# Controller-Board_Rack-PDU_2_0.net
KiCad netlist of a schematic drawn in EAGLE
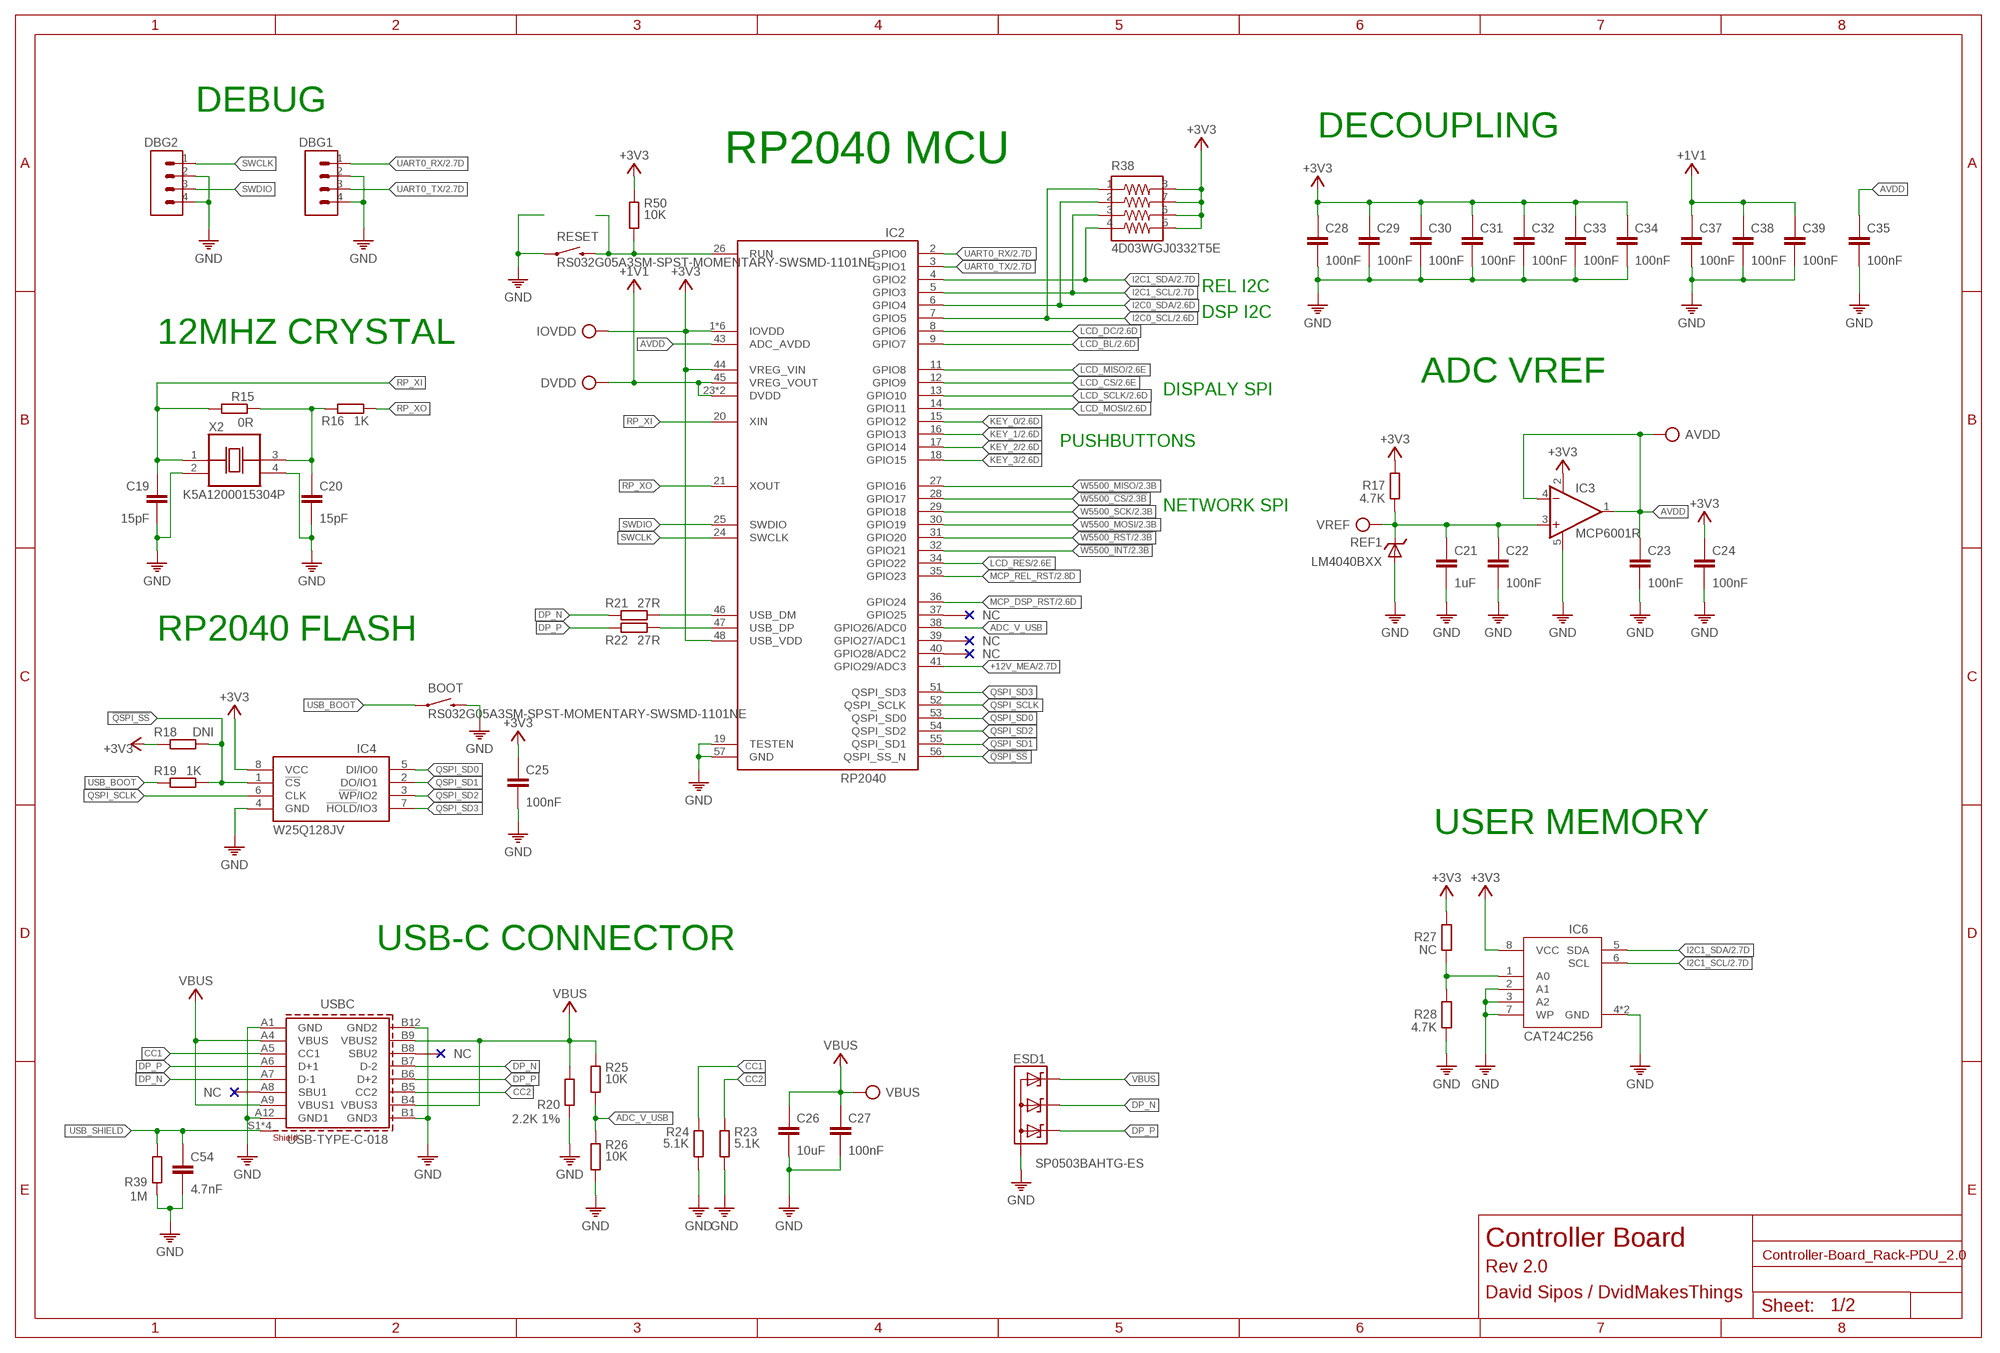
[diagram p0: schematic, sheet 1]
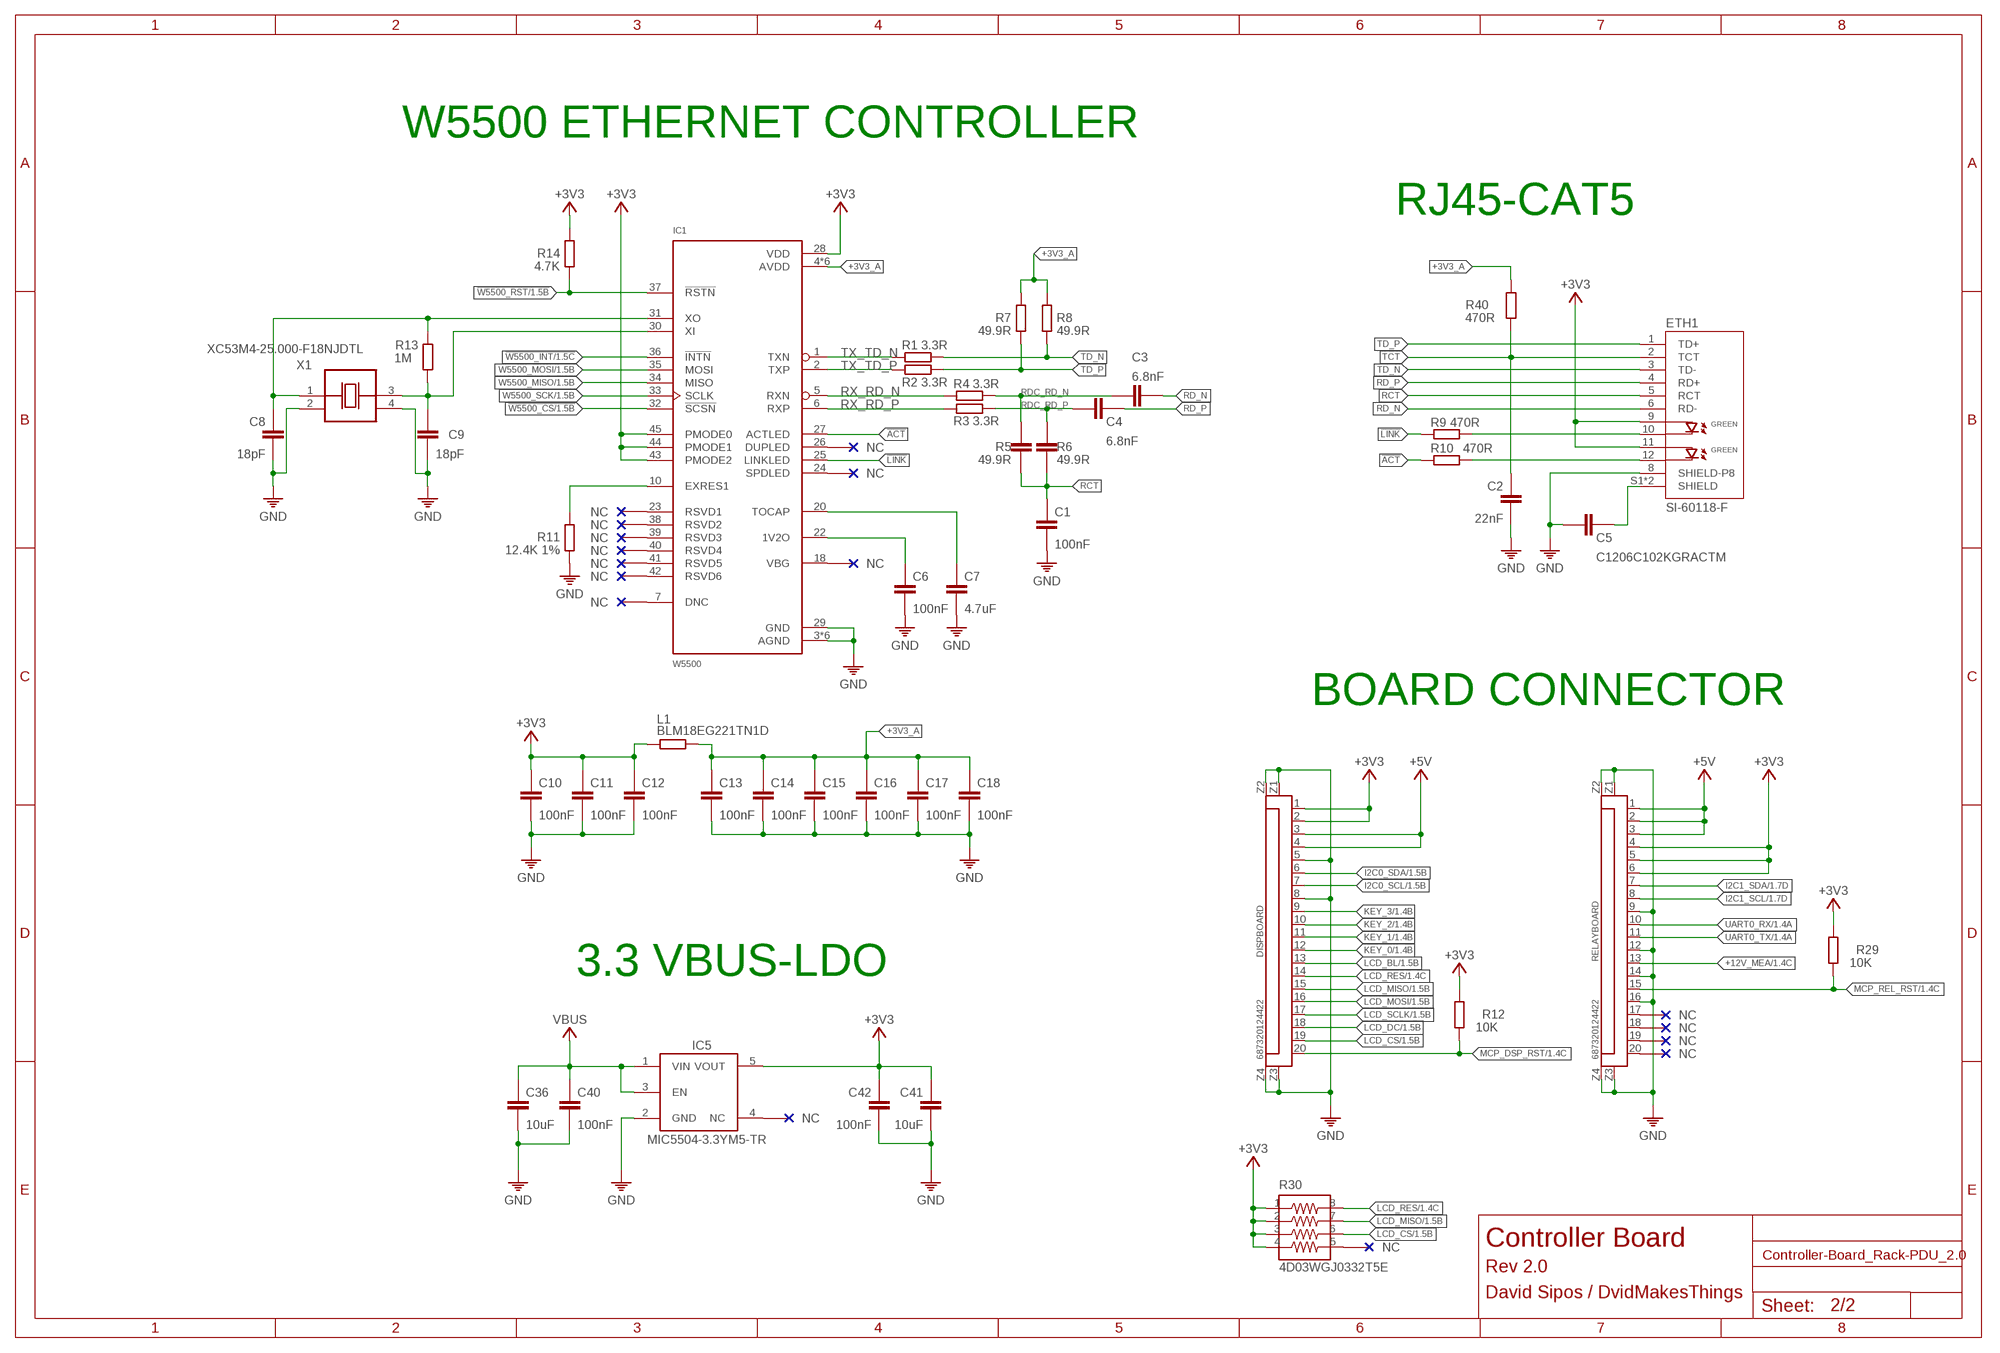
[diagram p1: schematic, sheet 2]

(export (version "E")
  (design (tool "Eeschema 10.0.6"))
  (components
    (comp (ref "C1")
      (value "100nF")
      (footprint "eagle-import:C0402")
      (libsource (lib "eagle-import") (part "C-0402"))
    )
    (comp (ref "C2")
      (value "22nF")
      (footprint "eagle-import:C0402")
      (libsource (lib "eagle-import") (part "C-0402"))
    )
    (comp (ref "C3")
      (value "6.8nF")
      (footprint "eagle-import:C0402")
      (libsource (lib "eagle-import") (part "C-0402"))
    )
    (comp (ref "C4")
      (value "6.8nF")
      (footprint "eagle-import:C0402")
      (libsource (lib "eagle-import") (part "C-0402"))
    )
    (comp (ref "C5")
      (value "C1206C102KGRACTM")
      (footprint "eagle-import:C1206")
      (libsource (lib "eagle-import") (part "C-1206"))
    )
    (comp (ref "C6")
      (value "100nF")
      (footprint "eagle-import:C0402")
      (libsource (lib "eagle-import") (part "C-0402"))
    )
    (comp (ref "C7")
      (value "4.7uF")
      (footprint "eagle-import:C0402")
      (libsource (lib "eagle-import") (part "C-0402"))
    )
    (comp (ref "C8")
      (value "18pF")
      (footprint "eagle-import:C0402")
      (libsource (lib "eagle-import") (part "C-0402"))
    )
    (comp (ref "C9")
      (value "18pF")
      (footprint "eagle-import:C0402")
      (libsource (lib "eagle-import") (part "C-0402"))
    )
    (comp (ref "C10")
      (value "100nF")
      (footprint "eagle-import:C0402")
      (libsource (lib "eagle-import") (part "C-0402"))
    )
    (comp (ref "C11")
      (value "100nF")
      (footprint "eagle-import:C0402")
      (libsource (lib "eagle-import") (part "C-0402"))
    )
    (comp (ref "C12")
      (value "100nF")
      (footprint "eagle-import:C0402")
      (libsource (lib "eagle-import") (part "C-0402"))
    )
    (comp (ref "C13")
      (value "100nF")
      (footprint "eagle-import:C0402")
      (libsource (lib "eagle-import") (part "C-0402"))
    )
    (comp (ref "C14")
      (value "100nF")
      (footprint "eagle-import:C0402")
      (libsource (lib "eagle-import") (part "C-0402"))
    )
    (comp (ref "C15")
      (value "100nF")
      (footprint "eagle-import:C0402")
      (libsource (lib "eagle-import") (part "C-0402"))
    )
    (comp (ref "C16")
      (value "100nF")
      (footprint "eagle-import:C0402")
      (libsource (lib "eagle-import") (part "C-0402"))
    )
    (comp (ref "C17")
      (value "100nF")
      (footprint "eagle-import:C0402")
      (libsource (lib "eagle-import") (part "C-0402"))
    )
    (comp (ref "C18")
      (value "100nF")
      (footprint "eagle-import:C0402")
      (libsource (lib "eagle-import") (part "C-0402"))
    )
    (comp (ref "C36")
      (value "10uF")
      (footprint "eagle-import:0805")
      (libsource (lib "eagle-import") (part "C0805"))
    )
    (comp (ref "C40")
      (value "100nF")
      (footprint "eagle-import:0402")
      (libsource (lib "eagle-import") (part "C0402"))
    )
    (comp (ref "C41")
      (value "10uF")
      (footprint "eagle-import:0805")
      (libsource (lib "eagle-import") (part "C0805"))
    )
    (comp (ref "C42")
      (value "100nF")
      (footprint "eagle-import:0402")
      (libsource (lib "eagle-import") (part "C0402"))
    )
    (comp (ref "DISPBOARD")
      (value "687320124422")
      (footprint "eagle-import:687320124422")
      (libsource (lib "eagle-import") (part "6873XX124422_687320124422"))
    )
    (comp (ref "ETH1")
      (value "SI-60118-F")
      (footprint "eagle-import:RJ45-CAT5")
      (fields (field (name "MANUFACTURER") "Bel Fuse"))
      (libsource (lib "eagle-import") (part "RJ45-CAT5"))
    )
    (comp (ref "IC1")
      (value "W5500")
      (footprint "eagle-import:LQFP48")
      (libsource (lib "eagle-import") (part "W5500"))
    )
    (comp (ref "IC5")
      (value "MIC5504-3.3YM5-TR")
      (footprint "eagle-import:SOT23-5")
      (libsource (lib "eagle-import") (part "MIC5504-3.3YM5-TR"))
    )
    (comp (ref "L1")
      (value "BLM18EG221TN1D")
      (footprint "eagle-import:0603")
      (libsource (lib "eagle-import") (part "R0603"))
    )
    (comp (ref "R1")
      (value "3.3R")
      (footprint "eagle-import:0402")
      (libsource (lib "eagle-import") (part "R0402"))
    )
    (comp (ref "R2")
      (value "3.3R")
      (footprint "eagle-import:0402")
      (libsource (lib "eagle-import") (part "R0402"))
    )
    (comp (ref "R3")
      (value "3.3R")
      (footprint "eagle-import:0402")
      (libsource (lib "eagle-import") (part "R0402"))
    )
    (comp (ref "R4")
      (value "3.3R")
      (footprint "eagle-import:0402")
      (libsource (lib "eagle-import") (part "R0402"))
    )
    (comp (ref "R5")
      (value "49.9R")
      (footprint "eagle-import:C0402")
      (libsource (lib "eagle-import") (part "C-0402"))
    )
    (comp (ref "R6")
      (value "49.9R")
      (footprint "eagle-import:C0402")
      (libsource (lib "eagle-import") (part "C-0402"))
    )
    (comp (ref "R7")
      (value "49.9R")
      (footprint "eagle-import:0402")
      (libsource (lib "eagle-import") (part "R0402"))
    )
    (comp (ref "R8")
      (value "49.9R")
      (footprint "eagle-import:0402")
      (libsource (lib "eagle-import") (part "R0402"))
    )
    (comp (ref "R9")
      (value "470R")
      (footprint "eagle-import:0402")
      (libsource (lib "eagle-import") (part "R0402"))
    )
    (comp (ref "R10")
      (value "470R")
      (footprint "eagle-import:0402")
      (libsource (lib "eagle-import") (part "R0402"))
    )
    (comp (ref "R11")
      (value "12.4K 1%")
      (footprint "eagle-import:0402")
      (libsource (lib "eagle-import") (part "R0402"))
    )
    (comp (ref "R12")
      (value "10K")
      (footprint "eagle-import:0402")
      (libsource (lib "eagle-import") (part "R0402"))
    )
    (comp (ref "R13")
      (value "1M")
      (footprint "eagle-import:0402")
      (libsource (lib "eagle-import") (part "R0402"))
    )
    (comp (ref "R14")
      (value "4.7K")
      (footprint "eagle-import:0402")
      (libsource (lib "eagle-import") (part "R0402"))
    )
    (comp (ref "R29")
      (value "10K")
      (footprint "eagle-import:0402")
      (libsource (lib "eagle-import") (part "R0402"))
    )
    (comp (ref "R30")
      (value "4D03WGJ0332T5E")
      (footprint "eagle-import:742C083103JP")
      (fields
        (field (name "MANUFACTURER") "CTS Resistor Products")
        (field (name "MPN") "742C083103JP")
        (field (name "CREATED_BY") "PCBLayout.com")
      )
      (libsource (lib "eagle-import") (part "742C083103JP"))
    )
    (comp (ref "R40")
      (value "470R")
      (footprint "eagle-import:0402")
      (libsource (lib "eagle-import") (part "R0402"))
    )
    (comp (ref "RELAYBOARD")
      (value "687320124422")
      (footprint "eagle-import:687320124422")
      (libsource (lib "eagle-import") (part "6873XX124422_687320124422"))
    )
    (comp (ref "X1")
      (value "XC53M4-25.000-F18NJDTL")
      (footprint "eagle-import:OSCCC500X320X130")
      (libsource (lib "eagle-import") (part "CRYSTAL"))
    )
    (comp (ref "AVDD")
      (value "TP")
      (footprint "eagle-import:TP")
      (libsource (lib "eagle-import") (part "TP"))
    )
    (comp (ref "BOOT")
      (value "RS032G05A3SM-SPST-MOMENTARY-SWSMD-1101NE")
      (footprint "eagle-import:TACTILE-SWITCH-1101NE")
      (libsource (lib "eagle-import") (part "RS032G05A3SM-SPST-MOMENTARY-SWSMD-1101NE"))
    )
    (comp (ref "C19")
      (value "15pF")
      (footprint "eagle-import:C0402")
      (libsource (lib "eagle-import") (part "C-0402"))
    )
    (comp (ref "C20")
      (value "15pF")
      (footprint "eagle-import:C0402")
      (libsource (lib "eagle-import") (part "C-0402"))
    )
    (comp (ref "C21")
      (value "1uF")
      (footprint "eagle-import:C0402")
      (libsource (lib "eagle-import") (part "C-0402"))
    )
    (comp (ref "C22")
      (value "100nF")
      (footprint "eagle-import:C0402")
      (libsource (lib "eagle-import") (part "C-0402"))
    )
    (comp (ref "C23")
      (value "100nF")
      (footprint "eagle-import:C0402")
      (libsource (lib "eagle-import") (part "C-0402"))
    )
    (comp (ref "C24")
      (value "100nF")
      (footprint "eagle-import:C0402")
      (libsource (lib "eagle-import") (part "C-0402"))
    )
    (comp (ref "C25")
      (value "100nF")
      (footprint "eagle-import:C0402")
      (libsource (lib "eagle-import") (part "C-0402"))
    )
    (comp (ref "C26")
      (value "10uF")
      (footprint "eagle-import:0805")
      (libsource (lib "eagle-import") (part "C0805"))
    )
    (comp (ref "C27")
      (value "100nF")
      (footprint "eagle-import:0402")
      (libsource (lib "eagle-import") (part "C0402"))
    )
    (comp (ref "C28")
      (value "100nF")
      (footprint "eagle-import:C0402")
      (libsource (lib "eagle-import") (part "C-0402"))
    )
    (comp (ref "C29")
      (value "100nF")
      (footprint "eagle-import:C0402")
      (libsource (lib "eagle-import") (part "C-0402"))
    )
    (comp (ref "C30")
      (value "100nF")
      (footprint "eagle-import:C0402")
      (libsource (lib "eagle-import") (part "C-0402"))
    )
    (comp (ref "C31")
      (value "100nF")
      (footprint "eagle-import:C0402")
      (libsource (lib "eagle-import") (part "C-0402"))
    )
    (comp (ref "C32")
      (value "100nF")
      (footprint "eagle-import:C0402")
      (libsource (lib "eagle-import") (part "C-0402"))
    )
    (comp (ref "C33")
      (value "100nF")
      (footprint "eagle-import:C0402")
      (libsource (lib "eagle-import") (part "C-0402"))
    )
    (comp (ref "C34")
      (value "100nF")
      (footprint "eagle-import:C0402")
      (libsource (lib "eagle-import") (part "C-0402"))
    )
    (comp (ref "C35")
      (value "100nF")
      (footprint "eagle-import:C0402")
      (libsource (lib "eagle-import") (part "C-0402"))
    )
    (comp (ref "C37")
      (value "100nF")
      (footprint "eagle-import:C0402")
      (libsource (lib "eagle-import") (part "C-0402"))
    )
    (comp (ref "C38")
      (value "100nF")
      (footprint "eagle-import:C0402")
      (libsource (lib "eagle-import") (part "C-0402"))
    )
    (comp (ref "C39")
      (value "100nF")
      (footprint "eagle-import:C0402")
      (libsource (lib "eagle-import") (part "C-0402"))
    )
    (comp (ref "C54")
      (value "4.7nF")
      (footprint "eagle-import:0402")
      (libsource (lib "eagle-import") (part "C0402"))
    )
    (comp (ref "DBG1")
      (value "CON-1X4")
      (footprint "eagle-import:1X4")
      (libsource (lib "eagle-import") (part "CON-1X4"))
    )
    (comp (ref "DBG2")
      (value "CON-1X4")
      (footprint "eagle-import:1X4")
      (libsource (lib "eagle-import") (part "CON-1X4"))
    )
    (comp (ref "DVDD")
      (value "TP")
      (footprint "eagle-import:TP")
      (libsource (lib "eagle-import") (part "TP"))
    )
    (comp (ref "ESD1")
      (value "SP0503BAHTG-ES")
      (footprint "eagle-import:SOT143")
      (libsource (lib "eagle-import") (part "SP0503BAHT"))
    )
    (comp (ref "IC2")
      (value "RP2040")
      (footprint "eagle-import:QFN40P700X700X100-57T510")
      (libsource (lib "eagle-import") (part "RP2040"))
    )
    (comp (ref "IC3")
      (value "MCP6001R")
      (footprint "eagle-import:SOT23-5")
      (libsource (lib "eagle-import") (part "MCP6001RT"))
    )
    (comp (ref "IC4")
      (value "W25Q128JVPIQ")
      (footprint "eagle-import:SON127P600X500X75-8N")
      (libsource (lib "eagle-import") (part "W25Q128JVP"))
    )
    (comp (ref "IC6")
      (value "CAT24C512HU5IGT3")
      (footprint "eagle-import:SON50P300X200X50-9T130X140N")
      (libsource (lib "eagle-import") (part "CAT24C256-HU4"))
    )
    (comp (ref "IOVDD")
      (value "TP")
      (footprint "eagle-import:TP")
      (libsource (lib "eagle-import") (part "TP"))
    )
    (comp (ref "R15")
      (value "0R")
      (footprint "eagle-import:0402")
      (libsource (lib "eagle-import") (part "R0402"))
    )
    (comp (ref "R16")
      (value "1K")
      (footprint "eagle-import:0402")
      (libsource (lib "eagle-import") (part "R0402"))
    )
    (comp (ref "R17")
      (value "4.7K")
      (footprint "eagle-import:0402")
      (libsource (lib "eagle-import") (part "R0402"))
    )
    (comp (ref "R18")
      (value "DNI")
      (footprint "eagle-import:0402")
      (libsource (lib "eagle-import") (part "R0402"))
    )
    (comp (ref "R19")
      (value "1K")
      (footprint "eagle-import:0402")
      (libsource (lib "eagle-import") (part "R0402"))
    )
    (comp (ref "R20")
      (value "2.2K 1%")
      (footprint "eagle-import:0402")
      (libsource (lib "eagle-import") (part "ds_passive_46685041_R0402"))
    )
    (comp (ref "R21")
      (value "27R")
      (footprint "eagle-import:0402")
      (libsource (lib "eagle-import") (part "R0402"))
    )
    (comp (ref "R22")
      (value "27R")
      (footprint "eagle-import:0402")
      (libsource (lib "eagle-import") (part "R0402"))
    )
    (comp (ref "R23")
      (value "5.1K")
      (footprint "eagle-import:0402")
      (libsource (lib "eagle-import") (part "ds_passive_46685041_R0402"))
    )
    (comp (ref "R24")
      (value "5.1K")
      (footprint "eagle-import:0402")
      (libsource (lib "eagle-import") (part "ds_passive_46685041_R0402"))
    )
    (comp (ref "R25")
      (value "10K")
      (footprint "eagle-import:0402")
      (libsource (lib "eagle-import") (part "ds_passive_46685041_R0402"))
    )
    (comp (ref "R26")
      (value "10K")
      (footprint "eagle-import:0402")
      (libsource (lib "eagle-import") (part "ds_passive_46685041_R0402"))
    )
    (comp (ref "R27")
      (value "NC")
      (footprint "eagle-import:0402")
      (libsource (lib "eagle-import") (part "R0402"))
    )
    (comp (ref "R28")
      (value "4.7K")
      (footprint "eagle-import:0402")
      (libsource (lib "eagle-import") (part "R0402"))
    )
    (comp (ref "R38")
      (value "4D03WGJ0332T5E")
      (footprint "eagle-import:742C083103JP")
      (fields
        (field (name "MANUFACTURER") "CTS Resistor Products")
        (field (name "MPN") "742C083103JP")
        (field (name "CREATED_BY") "PCBLayout.com")
      )
      (libsource (lib "eagle-import") (part "742C083103JP"))
    )
    (comp (ref "R39")
      (value "1M")
      (footprint "eagle-import:0402")
      (libsource (lib "eagle-import") (part "ds_passive_46685041_R0402"))
    )
    (comp (ref "R50")
      (value "10K")
      (footprint "eagle-import:0402")
      (libsource (lib "eagle-import") (part "ds_passive_46685041_R0402"))
    )
    (comp (ref "REF1")
      (value "LM4040BXX")
      (footprint "eagle-import:SOT23")
      (libsource (lib "eagle-import") (part "LM4040BXX"))
    )
    (comp (ref "RESET")
      (value "RS032G05A3SM-SPST-MOMENTARY-SWSMD-1101NE")
      (footprint "eagle-import:TACTILE-SWITCH-1101NE")
      (libsource (lib "eagle-import") (part "RS032G05A3SM-SPST-MOMENTARY-SWSMD-1101NE"))
    )
    (comp (ref "USBC")
      (value "USB-TYPE-C-018")
      (footprint "eagle-import:629722000214")
      (libsource (lib "eagle-import") (part "629722000214"))
    )
    (comp (ref "VBUS")
      (value "TP")
      (footprint "eagle-import:TP")
      (libsource (lib "eagle-import") (part "TP"))
    )
    (comp (ref "VREF")
      (value "TP")
      (footprint "eagle-import:TP")
      (libsource (lib "eagle-import") (part "TP"))
    )
    (comp (ref "X2")
      (value "K5A1200015304P")
      (footprint "eagle-import:OSCCC500X320X130")
      (libsource (lib "eagle-import") (part "CRYSTAL"))
    )
  )
  (nets
    (net (code "1") (name "+1V1") (class "Default")
      (node (ref "C37") (pin "1") (pinfunction "1_1") (pintype "passive"))
      (node (ref "C38") (pin "1") (pinfunction "1_1") (pintype "passive"))
      (node (ref "C39") (pin "1") (pinfunction "1_1") (pintype "passive"))
      (node (ref "DVDD") (pin "TP") (pinfunction "P$1_TP") (pintype "bidirectional"))
      (node (ref "IC2") (pin "23") (pinfunction "DVDD_23") (pintype "bidirectional"))
      (node (ref "IC2") (pin "45") (pinfunction "VREG_VOUT_45") (pintype "bidirectional"))
      (node (ref "IC2") (pin "50") (pinfunction "DVDD_50") (pintype "bidirectional"))
    )
    (net (code "2") (name "+3V3") (class "Default")
      (node (ref "C10") (pin "1") (pinfunction "1_1") (pintype "passive"))
      (node (ref "C11") (pin "1") (pinfunction "1_1") (pintype "passive"))
      (node (ref "C12") (pin "1") (pinfunction "1_1") (pintype "passive"))
      (node (ref "C24") (pin "1") (pinfunction "1_1") (pintype "passive"))
      (node (ref "C25") (pin "1") (pinfunction "1_1") (pintype "passive"))
      (node (ref "C28") (pin "1") (pinfunction "1_1") (pintype "passive"))
      (node (ref "C29") (pin "1") (pinfunction "1_1") (pintype "passive"))
      (node (ref "C30") (pin "1") (pinfunction "1_1") (pintype "passive"))
      (node (ref "C31") (pin "1") (pinfunction "1_1") (pintype "passive"))
      (node (ref "C32") (pin "1") (pinfunction "1_1") (pintype "passive"))
      (node (ref "C33") (pin "1") (pinfunction "1_1") (pintype "passive"))
      (node (ref "C34") (pin "1") (pinfunction "1_1") (pintype "passive"))
      (node (ref "C41") (pin "1") (pinfunction "1_1") (pintype "passive"))
      (node (ref "C42") (pin "1") (pinfunction "1_1") (pintype "passive"))
      (node (ref "DISPBOARD") (pin "1") (pinfunction "1_1") (pintype "passive"))
      (node (ref "DISPBOARD") (pin "2") (pinfunction "2_2") (pintype "passive"))
      (node (ref "ETH1") (pin "11") (pinfunction "GA2_11") (pintype "passive"))
      (node (ref "ETH1") (pin "9") (pinfunction "GA1_9") (pintype "passive"))
      (node (ref "IC1") (pin "28") (pinfunction "VDD_28") (pintype "power_in"))
      (node (ref "IC1") (pin "43") (pinfunction "PMODE2_43") (pintype "input"))
      (node (ref "IC1") (pin "44") (pinfunction "PMODE1_44") (pintype "input"))
      (node (ref "IC1") (pin "45") (pinfunction "PMODE0_45") (pintype "input"))
      (node (ref "IC2") (pin "1") (pinfunction "IOVDD_1") (pintype "bidirectional"))
      (node (ref "IC2") (pin "10") (pinfunction "IOVDD_10") (pintype "bidirectional"))
      (node (ref "IC2") (pin "22") (pinfunction "IOVDD_22") (pintype "bidirectional"))
      (node (ref "IC2") (pin "33") (pinfunction "IOVDD_33") (pintype "bidirectional"))
      (node (ref "IC2") (pin "42") (pinfunction "IOVDD_42") (pintype "bidirectional"))
      (node (ref "IC2") (pin "44") (pinfunction "VREG_VIN_44") (pintype "bidirectional"))
      (node (ref "IC2") (pin "48") (pinfunction "USB_VDD_48") (pintype "bidirectional"))
      (node (ref "IC2") (pin "49") (pinfunction "IOVDD_49") (pintype "bidirectional"))
      (node (ref "IC3") (pin "2") (pinfunction "V+_2") (pintype "power_in"))
      (node (ref "IC4") (pin "8") (pinfunction "VCC_8") (pintype "power_in"))
      (node (ref "IC5") (pin "5") (pinfunction "VOUT_5") (pintype "bidirectional"))
      (node (ref "IC6") (pin "8") (pinfunction "VCC_8") (pintype "power_in"))
      (node (ref "IOVDD") (pin "TP") (pinfunction "P$1_TP") (pintype "bidirectional"))
      (node (ref "L1") (pin "1") (pinfunction "1_1") (pintype "passive"))
      (node (ref "R12") (pin "2") (pinfunction "2_2") (pintype "passive"))
      (node (ref "R14") (pin "2") (pinfunction "2_2") (pintype "passive"))
      (node (ref "R17") (pin "2") (pinfunction "2_2") (pintype "passive"))
      (node (ref "R18") (pin "2") (pinfunction "2_2") (pintype "passive"))
      (node (ref "R27") (pin "2") (pinfunction "2_2") (pintype "passive"))
      (node (ref "R29") (pin "2") (pinfunction "2_2") (pintype "passive"))
      (node (ref "R30") (pin "1") (pinfunction "1_1") (pintype "passive"))
      (node (ref "R30") (pin "2") (pinfunction "2_2") (pintype "passive"))
      (node (ref "R30") (pin "3") (pinfunction "3_3") (pintype "passive"))
      (node (ref "R30") (pin "4") (pinfunction "4_4") (pintype "passive"))
      (node (ref "R38") (pin "5") (pinfunction "5_5") (pintype "passive"))
      (node (ref "R38") (pin "6") (pinfunction "6_6") (pintype "passive"))
      (node (ref "R38") (pin "7") (pinfunction "7_7") (pintype "passive"))
      (node (ref "R38") (pin "8") (pinfunction "8_8") (pintype "passive"))
      (node (ref "R50") (pin "1") (pinfunction "1_1") (pintype "passive"))
      (node (ref "RELAYBOARD") (pin "4") (pinfunction "4_4") (pintype "passive"))
      (node (ref "RELAYBOARD") (pin "5") (pinfunction "5_5") (pintype "passive"))
      (node (ref "RELAYBOARD") (pin "6") (pinfunction "6_6") (pintype "passive"))
    )
    (net (code "3") (name "+3V3_A") (class "Default")
      (node (ref "C13") (pin "1") (pinfunction "1_1") (pintype "passive"))
      (node (ref "C14") (pin "1") (pinfunction "1_1") (pintype "passive"))
      (node (ref "C15") (pin "1") (pinfunction "1_1") (pintype "passive"))
      (node (ref "C16") (pin "1") (pinfunction "1_1") (pintype "passive"))
      (node (ref "C17") (pin "1") (pinfunction "1_1") (pintype "passive"))
      (node (ref "C18") (pin "1") (pinfunction "1_1") (pintype "passive"))
      (node (ref "IC1") (pin "11") (pinfunction "AVDD_11") (pintype "power_in"))
      (node (ref "IC1") (pin "15") (pinfunction "AVDD_15") (pintype "power_in"))
      (node (ref "IC1") (pin "17") (pinfunction "AVDD_17") (pintype "power_in"))
      (node (ref "IC1") (pin "21") (pinfunction "AVDD_21") (pintype "power_in"))
      (node (ref "IC1") (pin "4") (pinfunction "AVDD_4") (pintype "power_in"))
      (node (ref "IC1") (pin "8") (pinfunction "AVDD_8") (pintype "power_in"))
      (node (ref "L1") (pin "2") (pinfunction "2_2") (pintype "passive"))
      (node (ref "R40") (pin "2") (pinfunction "2_2") (pintype "passive"))
      (node (ref "R7") (pin "2") (pinfunction "2_2") (pintype "passive"))
      (node (ref "R8") (pin "2") (pinfunction "2_2") (pintype "passive"))
    )
    (net (code "4") (name "+5V") (class "Default")
      (node (ref "DISPBOARD") (pin "3") (pinfunction "3_3") (pintype "passive"))
      (node (ref "DISPBOARD") (pin "4") (pinfunction "4_4") (pintype "passive"))
      (node (ref "RELAYBOARD") (pin "1") (pinfunction "1_1") (pintype "passive"))
      (node (ref "RELAYBOARD") (pin "2") (pinfunction "2_2") (pintype "passive"))
      (node (ref "RELAYBOARD") (pin "3") (pinfunction "3_3") (pintype "passive"))
    )
    (net (code "5") (name "+12V_MEA") (class "Default")
      (node (ref "IC2") (pin "41") (pinfunction "GPIO29/ADC3_41") (pintype "bidirectional"))
      (node (ref "RELAYBOARD") (pin "13") (pinfunction "13_13") (pintype "passive"))
    )
    (net (code "6") (name "ADC_V_USB") (class "Default")
      (node (ref "IC2") (pin "38") (pinfunction "GPIO26/ADC0_38") (pintype "bidirectional"))
      (node (ref "R25") (pin "2") (pinfunction "2_2") (pintype "passive"))
      (node (ref "R26") (pin "1") (pinfunction "1_1") (pintype "passive"))
    )
    (net (code "7") (name "AVDD") (class "Default")
      (node (ref "AVDD") (pin "TP") (pinfunction "P$1_TP") (pintype "bidirectional"))
      (node (ref "C23") (pin "1") (pinfunction "1_1") (pintype "passive"))
      (node (ref "C35") (pin "1") (pinfunction "1_1") (pintype "passive"))
      (node (ref "IC2") (pin "43") (pinfunction "ADC_AVDD_43") (pintype "bidirectional"))
      (node (ref "IC3") (pin "1") (pinfunction "OUT_1") (pintype "output"))
      (node (ref "IC3") (pin "4") (pinfunction "-IN_4") (pintype "input"))
    )
    (net (code "8") (name "CC1") (class "Default")
      (node (ref "R24") (pin "1") (pinfunction "1_1") (pintype "passive"))
      (node (ref "USBC") (pin "A5") (pinfunction "CC1_A5") (pintype "passive"))
    )
    (net (code "9") (name "CC2") (class "Default")
      (node (ref "R23") (pin "1") (pinfunction "1_1") (pintype "passive"))
      (node (ref "USBC") (pin "B5") (pinfunction "CC2_B5") (pintype "passive"))
    )
    (net (code "10") (name "DP_N") (class "Default")
      (node (ref "ESD1") (pin "3") (pinfunction "C2_3") (pintype "bidirectional"))
      (node (ref "R21") (pin "1") (pinfunction "1_1") (pintype "passive"))
      (node (ref "USBC") (pin "A7") (pinfunction "D-1_A7") (pintype "passive"))
      (node (ref "USBC") (pin "B7") (pinfunction "D-2_B7") (pintype "passive"))
    )
    (net (code "11") (name "DP_P") (class "Default")
      (node (ref "ESD1") (pin "2") (pinfunction "C1_2") (pintype "bidirectional"))
      (node (ref "R22") (pin "1") (pinfunction "1_1") (pintype "passive"))
      (node (ref "USBC") (pin "A6") (pinfunction "D+1_A6") (pintype "passive"))
      (node (ref "USBC") (pin "B6") (pinfunction "D+2_B6") (pintype "passive"))
    )
    (net (code "12") (name "GND") (class "Default")
      (node (ref "BOOT") (pin "2") (pinfunction "2_2") (pintype "passive"))
      (node (ref "C1") (pin "2") (pinfunction "2_2") (pintype "passive"))
      (node (ref "C10") (pin "2") (pinfunction "2_2") (pintype "passive"))
      (node (ref "C11") (pin "2") (pinfunction "2_2") (pintype "passive"))
      (node (ref "C12") (pin "2") (pinfunction "2_2") (pintype "passive"))
      (node (ref "C13") (pin "2") (pinfunction "2_2") (pintype "passive"))
      (node (ref "C14") (pin "2") (pinfunction "2_2") (pintype "passive"))
      (node (ref "C15") (pin "2") (pinfunction "2_2") (pintype "passive"))
      (node (ref "C16") (pin "2") (pinfunction "2_2") (pintype "passive"))
      (node (ref "C17") (pin "2") (pinfunction "2_2") (pintype "passive"))
      (node (ref "C18") (pin "2") (pinfunction "2_2") (pintype "passive"))
      (node (ref "C19") (pin "2") (pinfunction "2_2") (pintype "passive"))
      (node (ref "C2") (pin "2") (pinfunction "2_2") (pintype "passive"))
      (node (ref "C20") (pin "2") (pinfunction "2_2") (pintype "passive"))
      (node (ref "C21") (pin "2") (pinfunction "2_2") (pintype "passive"))
      (node (ref "C22") (pin "2") (pinfunction "2_2") (pintype "passive"))
      (node (ref "C23") (pin "2") (pinfunction "2_2") (pintype "passive"))
      (node (ref "C24") (pin "2") (pinfunction "2_2") (pintype "passive"))
      (node (ref "C25") (pin "2") (pinfunction "2_2") (pintype "passive"))
      (node (ref "C26") (pin "2") (pinfunction "2_2") (pintype "passive"))
      (node (ref "C27") (pin "2") (pinfunction "2_2") (pintype "passive"))
      (node (ref "C28") (pin "2") (pinfunction "2_2") (pintype "passive"))
      (node (ref "C29") (pin "2") (pinfunction "2_2") (pintype "passive"))
      (node (ref "C30") (pin "2") (pinfunction "2_2") (pintype "passive"))
      (node (ref "C31") (pin "2") (pinfunction "2_2") (pintype "passive"))
      (node (ref "C32") (pin "2") (pinfunction "2_2") (pintype "passive"))
      (node (ref "C33") (pin "2") (pinfunction "2_2") (pintype "passive"))
      (node (ref "C34") (pin "2") (pinfunction "2_2") (pintype "passive"))
      (node (ref "C35") (pin "2") (pinfunction "2_2") (pintype "passive"))
      (node (ref "C36") (pin "2") (pinfunction "2_2") (pintype "passive"))
      (node (ref "C37") (pin "2") (pinfunction "2_2") (pintype "passive"))
      (node (ref "C38") (pin "2") (pinfunction "2_2") (pintype "passive"))
      (node (ref "C39") (pin "2") (pinfunction "2_2") (pintype "passive"))
      (node (ref "C40") (pin "2") (pinfunction "2_2") (pintype "passive"))
      (node (ref "C41") (pin "2") (pinfunction "2_2") (pintype "passive"))
      (node (ref "C42") (pin "2") (pinfunction "2_2") (pintype "passive"))
      (node (ref "C5") (pin "1") (pinfunction "1_1") (pintype "passive"))
      (node (ref "C54") (pin "2") (pinfunction "2_2") (pintype "passive"))
      (node (ref "C6") (pin "2") (pinfunction "2_2") (pintype "passive"))
      (node (ref "C7") (pin "2") (pinfunction "2_2") (pintype "passive"))
      (node (ref "C8") (pin "2") (pinfunction "2_2") (pintype "passive"))
      (node (ref "C9") (pin "2") (pinfunction "2_2") (pintype "passive"))
      (node (ref "DBG1") (pin "2") (pinfunction "P$2_2") (pintype "bidirectional"))
      (node (ref "DBG1") (pin "4") (pinfunction "P$4_4") (pintype "bidirectional"))
      (node (ref "DBG2") (pin "2") (pinfunction "P$2_2") (pintype "bidirectional"))
      (node (ref "DBG2") (pin "4") (pinfunction "P$4_4") (pintype "bidirectional"))
      (node (ref "DISPBOARD") (pin "5") (pinfunction "5_5") (pintype "passive"))
      (node (ref "DISPBOARD") (pin "8") (pinfunction "8_8") (pintype "passive"))
      (node (ref "DISPBOARD") (pin "Z1") (pinfunction "Z1_Z1") (pintype "passive"))
      (node (ref "DISPBOARD") (pin "Z2") (pinfunction "Z2_Z2") (pintype "passive"))
      (node (ref "DISPBOARD") (pin "Z3") (pinfunction "Z3_Z3") (pintype "passive"))
      (node (ref "DISPBOARD") (pin "Z4") (pinfunction "Z4_Z4") (pintype "passive"))
      (node (ref "ESD1") (pin "1") (pinfunction "A_1") (pintype "bidirectional"))
      (node (ref "ETH1") (pin "8") (pinfunction "SHIELD-P8_8") (pintype "passive"))
      (node (ref "IC1") (pin "14") (pinfunction "AGND_14") (pintype "power_in"))
      (node (ref "IC1") (pin "16") (pinfunction "AGND_16") (pintype "power_in"))
      (node (ref "IC1") (pin "19") (pinfunction "AGND_19") (pintype "power_in"))
      (node (ref "IC1") (pin "29") (pinfunction "GND_29") (pintype "passive"))
      (node (ref "IC1") (pin "3") (pinfunction "AGND_3") (pintype "power_in"))
      (node (ref "IC1") (pin "48") (pinfunction "AGND_48") (pintype "power_in"))
      (node (ref "IC1") (pin "9") (pinfunction "AGND_9") (pintype "power_in"))
      (node (ref "IC2") (pin "19") (pinfunction "TESTEN_19") (pintype "bidirectional"))
      (node (ref "IC2") (pin "57") (pinfunction "GND_57") (pintype "bidirectional"))
      (node (ref "IC3") (pin "5") (pinfunction "V-_5") (pintype "power_in"))
      (node (ref "IC4") (pin "4") (pinfunction "GND_4") (pintype "power_in"))
      (node (ref "IC5") (pin "2") (pinfunction "GND_2") (pintype "bidirectional"))
      (node (ref "IC6") (pin "2") (pinfunction "A1_2") (pintype "bidirectional"))
      (node (ref "IC6") (pin "3") (pinfunction "A2_3") (pintype "bidirectional"))
      (node (ref "IC6") (pin "4") (pinfunction "GND_4") (pintype "power_in"))
      (node (ref "IC6") (pin "7") (pinfunction "WP_7") (pintype "bidirectional"))
      (node (ref "IC6") (pin "9") (pinfunction "GND_9") (pintype "power_in"))
      (node (ref "R11") (pin "1") (pinfunction "1_1") (pintype "passive"))
      (node (ref "R20") (pin "2") (pinfunction "2_2") (pintype "passive"))
      (node (ref "R23") (pin "2") (pinfunction "2_2") (pintype "passive"))
      (node (ref "R24") (pin "2") (pinfunction "2_2") (pintype "passive"))
      (node (ref "R26") (pin "2") (pinfunction "2_2") (pintype "passive"))
      (node (ref "R28") (pin "1") (pinfunction "1_1") (pintype "passive"))
      (node (ref "R39") (pin "2") (pinfunction "2_2") (pintype "passive"))
      (node (ref "REF1") (pin "2") (pinfunction "A_2") (pintype "passive"))
      (node (ref "REF1") (pin "3") (pinfunction "A_3") (pintype "passive"))
      (node (ref "RELAYBOARD") (pin "12") (pinfunction "12_12") (pintype "passive"))
      (node (ref "RELAYBOARD") (pin "14") (pinfunction "14_14") (pintype "passive"))
      (node (ref "RELAYBOARD") (pin "16") (pinfunction "16_16") (pintype "passive"))
      (node (ref "RELAYBOARD") (pin "9") (pinfunction "9_9") (pintype "passive"))
      (node (ref "RELAYBOARD") (pin "Z1") (pinfunction "Z1_Z1") (pintype "passive"))
      (node (ref "RELAYBOARD") (pin "Z2") (pinfunction "Z2_Z2") (pintype "passive"))
      (node (ref "RELAYBOARD") (pin "Z3") (pinfunction "Z3_Z3") (pintype "passive"))
      (node (ref "RELAYBOARD") (pin "Z4") (pinfunction "Z4_Z4") (pintype "passive"))
      (node (ref "RESET") (pin "1") (pinfunction "1_1") (pintype "passive"))
      (node (ref "USBC") (pin "A1") (pinfunction "GND_A1") (pintype "passive"))
      (node (ref "USBC") (pin "A12") (pinfunction "GND1_A12") (pintype "passive"))
      (node (ref "USBC") (pin "B1") (pinfunction "GND3_B1") (pintype "passive"))
      (node (ref "USBC") (pin "B12") (pinfunction "GND2_B12") (pintype "passive"))
      (node (ref "X1") (pin "2") (pinfunction "VSS_2") (pintype "power_in"))
      (node (ref "X1") (pin "4") (pinfunction "VDD_4") (pintype "power_in"))
      (node (ref "X2") (pin "2") (pinfunction "VSS_2") (pintype "power_in"))
      (node (ref "X2") (pin "4") (pinfunction "VDD_4") (pintype "power_in"))
    )
    (net (code "13") (name "I2C0_SCL") (class "Default")
      (node (ref "DISPBOARD") (pin "7") (pinfunction "7_7") (pintype "passive"))
      (node (ref "IC2") (pin "7") (pinfunction "GPIO5_7") (pintype "bidirectional"))
      (node (ref "R38") (pin "1") (pinfunction "1_1") (pintype "passive"))
    )
    (net (code "14") (name "I2C0_SDA") (class "Default")
      (node (ref "DISPBOARD") (pin "6") (pinfunction "6_6") (pintype "passive"))
      (node (ref "IC2") (pin "6") (pinfunction "GPIO4_6") (pintype "bidirectional"))
      (node (ref "R38") (pin "2") (pinfunction "2_2") (pintype "passive"))
    )
    (net (code "15") (name "I2C1_SCL") (class "Default")
      (node (ref "IC2") (pin "5") (pinfunction "GPIO3_5") (pintype "bidirectional"))
      (node (ref "IC6") (pin "6") (pinfunction "SCL_6") (pintype "bidirectional"))
      (node (ref "R38") (pin "3") (pinfunction "3_3") (pintype "passive"))
      (node (ref "RELAYBOARD") (pin "8") (pinfunction "8_8") (pintype "passive"))
    )
    (net (code "16") (name "I2C1_SDA") (class "Default")
      (node (ref "IC2") (pin "4") (pinfunction "GPIO2_4") (pintype "bidirectional"))
      (node (ref "IC6") (pin "5") (pinfunction "SDA_5") (pintype "bidirectional"))
      (node (ref "R38") (pin "4") (pinfunction "4_4") (pintype "passive"))
      (node (ref "RELAYBOARD") (pin "7") (pinfunction "7_7") (pintype "passive"))
    )
    (net (code "17") (name "KEY_0") (class "Default")
      (node (ref "DISPBOARD") (pin "12") (pinfunction "12_12") (pintype "passive"))
      (node (ref "IC2") (pin "15") (pinfunction "GPIO12_15") (pintype "bidirectional"))
    )
    (net (code "18") (name "KEY_1") (class "Default")
      (node (ref "DISPBOARD") (pin "11") (pinfunction "11_11") (pintype "passive"))
      (node (ref "IC2") (pin "16") (pinfunction "GPIO13_16") (pintype "bidirectional"))
    )
    (net (code "19") (name "KEY_2") (class "Default")
      (node (ref "DISPBOARD") (pin "10") (pinfunction "10_10") (pintype "passive"))
      (node (ref "IC2") (pin "17") (pinfunction "GPIO14_17") (pintype "bidirectional"))
    )
    (net (code "20") (name "KEY_3") (class "Default")
      (node (ref "DISPBOARD") (pin "9") (pinfunction "9_9") (pintype "passive"))
      (node (ref "IC2") (pin "18") (pinfunction "GPIO15_18") (pintype "bidirectional"))
    )
    (net (code "21") (name "LCD_BL") (class "Default")
      (node (ref "DISPBOARD") (pin "13") (pinfunction "13_13") (pintype "passive"))
      (node (ref "IC2") (pin "9") (pinfunction "GPIO7_9") (pintype "bidirectional"))
    )
    (net (code "22") (name "LCD_CS") (class "Default")
      (node (ref "DISPBOARD") (pin "19") (pinfunction "19_19") (pintype "passive"))
      (node (ref "IC2") (pin "12") (pinfunction "GPIO9_12") (pintype "bidirectional"))
      (node (ref "R30") (pin "6") (pinfunction "6_6") (pintype "passive"))
    )
    (net (code "23") (name "LCD_DC") (class "Default")
      (node (ref "DISPBOARD") (pin "18") (pinfunction "18_18") (pintype "passive"))
      (node (ref "IC2") (pin "8") (pinfunction "GPIO6_8") (pintype "bidirectional"))
    )
    (net (code "24") (name "LCD_MISO") (class "Default")
      (node (ref "DISPBOARD") (pin "15") (pinfunction "15_15") (pintype "passive"))
      (node (ref "IC2") (pin "11") (pinfunction "GPIO8_11") (pintype "bidirectional"))
      (node (ref "R30") (pin "7") (pinfunction "7_7") (pintype "passive"))
    )
    (net (code "25") (name "LCD_MOSI") (class "Default")
      (node (ref "DISPBOARD") (pin "16") (pinfunction "16_16") (pintype "passive"))
      (node (ref "IC2") (pin "14") (pinfunction "GPIO11_14") (pintype "bidirectional"))
    )
    (net (code "26") (name "LCD_RES") (class "Default")
      (node (ref "DISPBOARD") (pin "14") (pinfunction "14_14") (pintype "passive"))
      (node (ref "IC2") (pin "34") (pinfunction "GPIO22_34") (pintype "bidirectional"))
      (node (ref "R30") (pin "8") (pinfunction "8_8") (pintype "passive"))
    )
    (net (code "27") (name "LCD_SCLK") (class "Default")
      (node (ref "DISPBOARD") (pin "17") (pinfunction "17_17") (pintype "passive"))
      (node (ref "IC2") (pin "13") (pinfunction "GPIO10_13") (pintype "bidirectional"))
    )
    (net (code "28") (name "MCP_DSP_RST") (class "Default")
      (node (ref "DISPBOARD") (pin "20") (pinfunction "20_20") (pintype "passive"))
      (node (ref "IC2") (pin "36") (pinfunction "GPIO24_36") (pintype "bidirectional"))
      (node (ref "R12") (pin "1") (pinfunction "1_1") (pintype "passive"))
    )
    (net (code "29") (name "MCP_REL_RST") (class "Default")
      (node (ref "IC2") (pin "35") (pinfunction "GPIO23_35") (pintype "bidirectional"))
      (node (ref "R29") (pin "1") (pinfunction "1_1") (pintype "passive"))
      (node (ref "RELAYBOARD") (pin "15") (pinfunction "15_15") (pintype "passive"))
    )
    (net (code "30") (name "Net-(C5-Pad2)") (class "Default")
      (node (ref "C5") (pin "2") (pinfunction "2_2") (pintype "passive"))
      (node (ref "ETH1") (pin "S1") (pinfunction "SHIELD_S1") (pintype "passive"))
      (node (ref "ETH1") (pin "S2") (pinfunction "SHIELD_S2") (pintype "passive"))
    )
    (net (code "31") (name "Net-(ETH1-GK1)") (class "Default")
      (node (ref "ETH1") (pin "10") (pinfunction "GK1_10") (pintype "passive"))
      (node (ref "R9") (pin "2") (pinfunction "2_2") (pintype "passive"))
    )
    (net (code "32") (name "Net-(ETH1-GK2)") (class "Default")
      (node (ref "ETH1") (pin "12") (pinfunction "GK2_12") (pintype "passive"))
      (node (ref "R10") (pin "2") (pinfunction "2_2") (pintype "passive"))
    )
    (net (code "33") (name "Net-(IC1-1V2O)") (class "Default")
      (node (ref "C6") (pin "1") (pinfunction "1_1") (pintype "passive"))
      (node (ref "IC1") (pin "22") (pinfunction "1V2O_22") (pintype "output"))
    )
    (net (code "34") (name "Net-(IC1-EXRES1)") (class "Default")
      (node (ref "IC1") (pin "10") (pinfunction "EXRES1_10") (pintype "bidirectional"))
      (node (ref "R11") (pin "2") (pinfunction "2_2") (pintype "passive"))
    )
    (net (code "35") (name "Net-(IC1-TOCAP)") (class "Default")
      (node (ref "C7") (pin "1") (pinfunction "1_1") (pintype "passive"))
      (node (ref "IC1") (pin "20") (pinfunction "TOCAP_20") (pintype "output"))
    )
    (net (code "36") (name "Net-(IC1-XI)") (class "Default")
      (node (ref "C9") (pin "1") (pinfunction "1_1") (pintype "passive"))
      (node (ref "IC1") (pin "30") (pinfunction "XI_30") (pintype "input"))
      (node (ref "R13") (pin "1") (pinfunction "1_1") (pintype "passive"))
      (node (ref "X1") (pin "3") (pinfunction "OUT_3") (pintype "output"))
    )
    (net (code "37") (name "Net-(IC1-XO)") (class "Default")
      (node (ref "C8") (pin "1") (pinfunction "1_1") (pintype "passive"))
      (node (ref "IC1") (pin "31") (pinfunction "XO_31") (pintype "output"))
      (node (ref "R13") (pin "2") (pinfunction "2_2") (pintype "passive"))
      (node (ref "X1") (pin "1") (pinfunction "CON_1") (pintype "input"))
    )
    (net (code "38") (name "Net-(IC2-RUN)") (class "Default")
      (node (ref "IC2") (pin "26") (pinfunction "RUN_26") (pintype "bidirectional"))
      (node (ref "R50") (pin "2") (pinfunction "2_2") (pintype "passive"))
      (node (ref "RESET") (pin "2") (pinfunction "2_2") (pintype "passive"))
    )
    (net (code "39") (name "Net-(IC2-USB_DM)") (class "Default")
      (node (ref "IC2") (pin "46") (pinfunction "USB_DM_46") (pintype "bidirectional"))
      (node (ref "R21") (pin "2") (pinfunction "2_2") (pintype "passive"))
    )
    (net (code "40") (name "Net-(IC2-USB_DP)") (class "Default")
      (node (ref "IC2") (pin "47") (pinfunction "USB_DP_47") (pintype "bidirectional"))
      (node (ref "R22") (pin "2") (pinfunction "2_2") (pintype "passive"))
    )
    (net (code "41") (name "Net-(IC3-+IN)") (class "Default")
      (node (ref "C21") (pin "1") (pinfunction "1_1") (pintype "passive"))
      (node (ref "C22") (pin "1") (pinfunction "1_1") (pintype "passive"))
      (node (ref "IC3") (pin "3") (pinfunction "+IN_3") (pintype "input"))
      (node (ref "R17") (pin "1") (pinfunction "1_1") (pintype "passive"))
      (node (ref "REF1") (pin "1") (pinfunction "C_1") (pintype "passive"))
      (node (ref "VREF") (pin "TP") (pinfunction "P$1_TP") (pintype "bidirectional"))
    )
    (net (code "42") (name "Net-(IC6-A0)") (class "Default")
      (node (ref "IC6") (pin "1") (pinfunction "A0_1") (pintype "bidirectional"))
      (node (ref "R27") (pin "1") (pinfunction "1_1") (pintype "passive"))
      (node (ref "R28") (pin "2") (pinfunction "2_2") (pintype "passive"))
    )
    (net (code "43") (name "Net-(X2-OUT)") (class "Default")
      (node (ref "C20") (pin "1") (pinfunction "1_1") (pintype "passive"))
      (node (ref "R15") (pin "2") (pinfunction "2_2") (pintype "passive"))
      (node (ref "R16") (pin "1") (pinfunction "1_1") (pintype "passive"))
      (node (ref "X2") (pin "3") (pinfunction "OUT_3") (pintype "output"))
    )
    (net (code "44") (name "QSPI_SCLK") (class "Default")
      (node (ref "IC2") (pin "52") (pinfunction "QSPI_SCLK_52") (pintype "bidirectional"))
      (node (ref "IC4") (pin "6") (pinfunction "CLK_6") (pintype "bidirectional"))
    )
    (net (code "45") (name "QSPI_SD0") (class "Default")
      (node (ref "IC2") (pin "53") (pinfunction "QSPI_SD0_53") (pintype "bidirectional"))
      (node (ref "IC4") (pin "5") (pinfunction "DI/IO0_5") (pintype "bidirectional"))
    )
    (net (code "46") (name "QSPI_SD1") (class "Default")
      (node (ref "IC2") (pin "55") (pinfunction "QSPI_SD1_55") (pintype "bidirectional"))
      (node (ref "IC4") (pin "2") (pinfunction "DO/IO1_2") (pintype "bidirectional"))
    )
    (net (code "47") (name "QSPI_SD2") (class "Default")
      (node (ref "IC2") (pin "54") (pinfunction "QSPI_SD2_54") (pintype "bidirectional"))
      (node (ref "IC4") (pin "3") (pinfunction "~{WP}/IO2_3") (pintype "bidirectional"))
    )
    (net (code "48") (name "QSPI_SD3") (class "Default")
      (node (ref "IC2") (pin "51") (pinfunction "QSPI_SD3_51") (pintype "bidirectional"))
      (node (ref "IC4") (pin "7") (pinfunction "~{HOLD}/IO3_7") (pintype "bidirectional"))
    )
    (net (code "49") (name "RCT") (class "Default")
      (node (ref "C1") (pin "1") (pinfunction "1_1") (pintype "passive"))
      (node (ref "ETH1") (pin "5") (pinfunction "RCT_5") (pintype "passive"))
      (node (ref "R5") (pin "1") (pinfunction "1_1") (pintype "passive"))
      (node (ref "R6") (pin "1") (pinfunction "1_1") (pintype "passive"))
    )
    (net (code "50") (name "RDC_RD_N") (class "Default")
      (node (ref "C3") (pin "1") (pinfunction "1_1") (pintype "passive"))
      (node (ref "R4") (pin "2") (pinfunction "2_2") (pintype "passive"))
      (node (ref "R5") (pin "2") (pinfunction "2_2") (pintype "passive"))
    )
    (net (code "51") (name "RDC_RD_P") (class "Default")
      (node (ref "C4") (pin "1") (pinfunction "1_1") (pintype "passive"))
      (node (ref "R3") (pin "2") (pinfunction "2_2") (pintype "passive"))
      (node (ref "R6") (pin "2") (pinfunction "2_2") (pintype "passive"))
    )
    (net (code "52") (name "RD_N") (class "Default")
      (node (ref "C3") (pin "2") (pinfunction "2_2") (pintype "passive"))
      (node (ref "ETH1") (pin "6") (pinfunction "RD-_6") (pintype "passive"))
    )
    (net (code "53") (name "RD_P") (class "Default")
      (node (ref "C4") (pin "2") (pinfunction "2_2") (pintype "passive"))
      (node (ref "ETH1") (pin "4") (pinfunction "RD+_4") (pintype "passive"))
    )
    (net (code "54") (name "RP_XI") (class "Default")
      (node (ref "C19") (pin "1") (pinfunction "1_1") (pintype "passive"))
      (node (ref "IC2") (pin "20") (pinfunction "XIN_20") (pintype "bidirectional"))
      (node (ref "R15") (pin "1") (pinfunction "1_1") (pintype "passive"))
      (node (ref "X2") (pin "1") (pinfunction "CON_1") (pintype "input"))
    )
    (net (code "55") (name "RP_XO") (class "Default")
      (node (ref "IC2") (pin "21") (pinfunction "XOUT_21") (pintype "bidirectional"))
      (node (ref "R16") (pin "2") (pinfunction "2_2") (pintype "passive"))
    )
    (net (code "56") (name "RX_RD_N") (class "Default")
      (node (ref "IC1") (pin "5") (pinfunction "RXN_5") (pintype "input"))
      (node (ref "R4") (pin "1") (pinfunction "1_1") (pintype "passive"))
    )
    (net (code "57") (name "RX_RD_P") (class "Default")
      (node (ref "IC1") (pin "6") (pinfunction "RXP_6") (pintype "input"))
      (node (ref "R3") (pin "1") (pinfunction "1_1") (pintype "passive"))
    )
    (net (code "58") (name "SWCLK") (class "Default")
      (node (ref "DBG2") (pin "1") (pinfunction "P$1_1") (pintype "bidirectional"))
      (node (ref "IC2") (pin "24") (pinfunction "SWCLK_24") (pintype "bidirectional"))
    )
    (net (code "59") (name "SWDIO") (class "Default")
      (node (ref "DBG2") (pin "3") (pinfunction "P$3_3") (pintype "bidirectional"))
      (node (ref "IC2") (pin "25") (pinfunction "SWDIO_25") (pintype "bidirectional"))
    )
    (net (code "60") (name "TCT") (class "Default")
      (node (ref "C2") (pin "1") (pinfunction "1_1") (pintype "passive"))
      (node (ref "ETH1") (pin "2") (pinfunction "TCT_2") (pintype "passive"))
      (node (ref "R40") (pin "1") (pinfunction "1_1") (pintype "passive"))
    )
    (net (code "61") (name "TD_N") (class "Default")
      (node (ref "ETH1") (pin "3") (pinfunction "TD-_3") (pintype "passive"))
      (node (ref "R1") (pin "2") (pinfunction "2_2") (pintype "passive"))
      (node (ref "R8") (pin "1") (pinfunction "1_1") (pintype "passive"))
    )
    (net (code "62") (name "TD_P") (class "Default")
      (node (ref "ETH1") (pin "1") (pinfunction "TD+_1") (pintype "passive"))
      (node (ref "R2") (pin "2") (pinfunction "2_2") (pintype "passive"))
      (node (ref "R7") (pin "1") (pinfunction "1_1") (pintype "passive"))
    )
    (net (code "63") (name "TX_TD_N") (class "Default")
      (node (ref "IC1") (pin "1") (pinfunction "TXN_1") (pintype "output"))
      (node (ref "R1") (pin "1") (pinfunction "1_1") (pintype "passive"))
    )
    (net (code "64") (name "TX_TD_P") (class "Default")
      (node (ref "IC1") (pin "2") (pinfunction "TXP_2") (pintype "output"))
      (node (ref "R2") (pin "1") (pinfunction "1_1") (pintype "passive"))
    )
    (net (code "65") (name "UART0_RX") (class "Default")
      (node (ref "DBG1") (pin "1") (pinfunction "P$1_1") (pintype "bidirectional"))
      (node (ref "IC2") (pin "2") (pinfunction "GPIO0_2") (pintype "bidirectional"))
      (node (ref "RELAYBOARD") (pin "10") (pinfunction "10_10") (pintype "passive"))
    )
    (net (code "66") (name "UART0_TX") (class "Default")
      (node (ref "DBG1") (pin "3") (pinfunction "P$3_3") (pintype "bidirectional"))
      (node (ref "IC2") (pin "3") (pinfunction "GPIO1_3") (pintype "bidirectional"))
      (node (ref "RELAYBOARD") (pin "11") (pinfunction "11_11") (pintype "passive"))
    )
    (net (code "67") (name "USB_BOOT") (class "Default")
      (node (ref "BOOT") (pin "1") (pinfunction "1_1") (pintype "passive"))
      (node (ref "R19") (pin "1") (pinfunction "1_1") (pintype "passive"))
    )
    (net (code "68") (name "USB_SHIELD") (class "Default")
      (node (ref "C54") (pin "1") (pinfunction "1_1") (pintype "passive"))
      (node (ref "R39") (pin "1") (pinfunction "1_1") (pintype "passive"))
      (node (ref "USBC") (pin "S1") (pinfunction "SHIELD_S1") (pintype "passive"))
      (node (ref "USBC") (pin "S2") (pinfunction "SHIELD_S2") (pintype "passive"))
      (node (ref "USBC") (pin "S3") (pinfunction "SHIELD_S3") (pintype "passive"))
      (node (ref "USBC") (pin "S4") (pinfunction "SHIELD_S4") (pintype "passive"))
    )
    (net (code "69") (name "VBUS") (class "Default")
      (node (ref "C26") (pin "1") (pinfunction "1_1") (pintype "passive"))
      (node (ref "C27") (pin "1") (pinfunction "1_1") (pintype "passive"))
      (node (ref "C36") (pin "1") (pinfunction "1_1") (pintype "passive"))
      (node (ref "C40") (pin "1") (pinfunction "1_1") (pintype "passive"))
      (node (ref "ESD1") (pin "4") (pinfunction "C3_4") (pintype "bidirectional"))
      (node (ref "IC5") (pin "1") (pinfunction "VIN_1") (pintype "bidirectional"))
      (node (ref "IC5") (pin "3") (pinfunction "EN_3") (pintype "bidirectional"))
      (node (ref "R20") (pin "1") (pinfunction "1_1") (pintype "passive"))
      (node (ref "R25") (pin "1") (pinfunction "1_1") (pintype "passive"))
      (node (ref "USBC") (pin "A4") (pinfunction "VBUS_A4") (pintype "passive"))
      (node (ref "USBC") (pin "A9") (pinfunction "VBUS1_A9") (pintype "passive"))
      (node (ref "USBC") (pin "B4") (pinfunction "VBUS3_B4") (pintype "passive"))
      (node (ref "USBC") (pin "B9") (pinfunction "VBUS2_B9") (pintype "passive"))
      (node (ref "VBUS") (pin "TP") (pinfunction "P$1_TP") (pintype "bidirectional"))
    )
    (net (code "70") (name "W5500_MISO") (class "Default")
      (node (ref "IC1") (pin "34") (pinfunction "MISO_34") (pintype "output"))
      (node (ref "IC2") (pin "27") (pinfunction "GPIO16_27") (pintype "bidirectional"))
    )
    (net (code "71") (name "W5500_MOSI") (class "Default")
      (node (ref "IC1") (pin "35") (pinfunction "MOSI_35") (pintype "input"))
      (node (ref "IC2") (pin "30") (pinfunction "GPIO19_30") (pintype "bidirectional"))
    )
    (net (code "72") (name "W5500_SCK") (class "Default")
      (node (ref "IC1") (pin "33") (pinfunction "SCLK_33") (pintype "input"))
      (node (ref "IC2") (pin "29") (pinfunction "GPIO18_29") (pintype "bidirectional"))
    )
    (net (code "73") (name "unconnected-(IC1-DNC-Pad7)") (class "Default")
      (node (ref "IC1") (pin "7") (pinfunction "DNC_7") (pintype "bidirectional"))
    )
    (net (code "74") (name "unconnected-(IC1-DUPLED-Pad26)") (class "Default")
      (node (ref "IC1") (pin "26") (pinfunction "DUPLED_26") (pintype "output"))
    )
    (net (code "75") (name "unconnected-(IC1-RSVD1-Pad23)") (class "Default")
      (node (ref "IC1") (pin "23") (pinfunction "RSVD1_23") (pintype "input"))
    )
    (net (code "76") (name "unconnected-(IC1-RSVD2-Pad38)") (class "Default")
      (node (ref "IC1") (pin "38") (pinfunction "RSVD2_38") (pintype "input"))
    )
    (net (code "77") (name "unconnected-(IC1-RSVD3-Pad39)") (class "Default")
      (node (ref "IC1") (pin "39") (pinfunction "RSVD3_39") (pintype "input"))
    )
    (net (code "78") (name "unconnected-(IC1-RSVD4-Pad40)") (class "Default")
      (node (ref "IC1") (pin "40") (pinfunction "RSVD4_40") (pintype "input"))
    )
    (net (code "79") (name "unconnected-(IC1-RSVD5-Pad41)") (class "Default")
      (node (ref "IC1") (pin "41") (pinfunction "RSVD5_41") (pintype "input"))
    )
    (net (code "80") (name "unconnected-(IC1-RSVD6-Pad42)") (class "Default")
      (node (ref "IC1") (pin "42") (pinfunction "RSVD6_42") (pintype "input"))
    )
    (net (code "81") (name "unconnected-(IC1-SPDLED-Pad24)") (class "Default")
      (node (ref "IC1") (pin "24") (pinfunction "SPDLED_24") (pintype "output"))
    )
    (net (code "82") (name "unconnected-(IC1-VBG-Pad18)") (class "Default")
      (node (ref "IC1") (pin "18") (pinfunction "VBG_18") (pintype "output"))
    )
    (net (code "83") (name "unconnected-(IC2-GPIO25-Pad37)") (class "Default")
      (node (ref "IC2") (pin "37") (pinfunction "GPIO25_37") (pintype "bidirectional"))
    )
    (net (code "84") (name "unconnected-(IC2-GPIO27{slash}ADC1-Pad39)") (class "Default")
      (node (ref "IC2") (pin "39") (pinfunction "GPIO27/ADC1_39") (pintype "bidirectional"))
    )
    (net (code "85") (name "unconnected-(IC2-GPIO28{slash}ADC2-Pad40)") (class "Default")
      (node (ref "IC2") (pin "40") (pinfunction "GPIO28/ADC2_40") (pintype "bidirectional"))
    )
    (net (code "86") (name "unconnected-(IC5-NC-Pad4)") (class "Default")
      (node (ref "IC5") (pin "4") (pinfunction "NC_4") (pintype "bidirectional"))
    )
    (net (code "87") (name "unconnected-(R30-Pad5)") (class "Default")
      (node (ref "R30") (pin "5") (pinfunction "5_5") (pintype "passive"))
    )
    (net (code "88") (name "unconnected-(RELAYBOARD-Pad17)") (class "Default")
      (node (ref "RELAYBOARD") (pin "17") (pinfunction "17_17") (pintype "passive"))
    )
    (net (code "89") (name "unconnected-(RELAYBOARD-Pad18)") (class "Default")
      (node (ref "RELAYBOARD") (pin "18") (pinfunction "18_18") (pintype "passive"))
    )
    (net (code "90") (name "unconnected-(RELAYBOARD-Pad19)") (class "Default")
      (node (ref "RELAYBOARD") (pin "19") (pinfunction "19_19") (pintype "passive"))
    )
    (net (code "91") (name "unconnected-(RELAYBOARD-Pad20)") (class "Default")
      (node (ref "RELAYBOARD") (pin "20") (pinfunction "20_20") (pintype "passive"))
    )
    (net (code "92") (name "unconnected-(USBC-SBU1-PadA8)") (class "Default")
      (node (ref "USBC") (pin "A8") (pinfunction "SBU1_A8") (pintype "passive"))
    )
    (net (code "93") (name "unconnected-(USBC-SBU2-PadB8)") (class "Default")
      (node (ref "USBC") (pin "B8") (pinfunction "SBU2_B8") (pintype "passive"))
    )
    (net (code "94") (name "~{ACT}") (class "Default")
      (node (ref "IC1") (pin "27") (pinfunction "ACTLED_27") (pintype "output"))
      (node (ref "R10") (pin "1") (pinfunction "1_1") (pintype "passive"))
    )
    (net (code "95") (name "~{LINK}") (class "Default")
      (node (ref "IC1") (pin "25") (pinfunction "LINKLED_25") (pintype "output"))
      (node (ref "R9") (pin "1") (pinfunction "1_1") (pintype "passive"))
    )
    (net (code "96") (name "~{QSPI_SS}") (class "Default")
      (node (ref "IC2") (pin "56") (pinfunction "QSPI_SS_N_56") (pintype "bidirectional"))
      (node (ref "IC4") (pin "1") (pinfunction "~{CS}_1") (pintype "bidirectional"))
      (node (ref "R18") (pin "1") (pinfunction "1_1") (pintype "passive"))
      (node (ref "R19") (pin "2") (pinfunction "2_2") (pintype "passive"))
    )
    (net (code "97") (name "~{W5500_CS}") (class "Default")
      (node (ref "IC1") (pin "32") (pinfunction "~{SCSN}_32") (pintype "input"))
      (node (ref "IC2") (pin "28") (pinfunction "GPIO17_28") (pintype "bidirectional"))
    )
    (net (code "98") (name "~{W5500_INT}") (class "Default")
      (node (ref "IC1") (pin "36") (pinfunction "~{INTN}_36") (pintype "input"))
      (node (ref "IC2") (pin "32") (pinfunction "GPIO21_32") (pintype "bidirectional"))
    )
    (net (code "99") (name "~{W5500_RST}") (class "Default")
      (node (ref "IC1") (pin "37") (pinfunction "~{RSTN}_37") (pintype "input"))
      (node (ref "IC2") (pin "31") (pinfunction "GPIO20_31") (pintype "bidirectional"))
      (node (ref "R14") (pin "1") (pinfunction "1_1") (pintype "passive"))
    )
  )
)
